# ASL1001.net
KiCad netlist of a schematic drawn in EAGLE
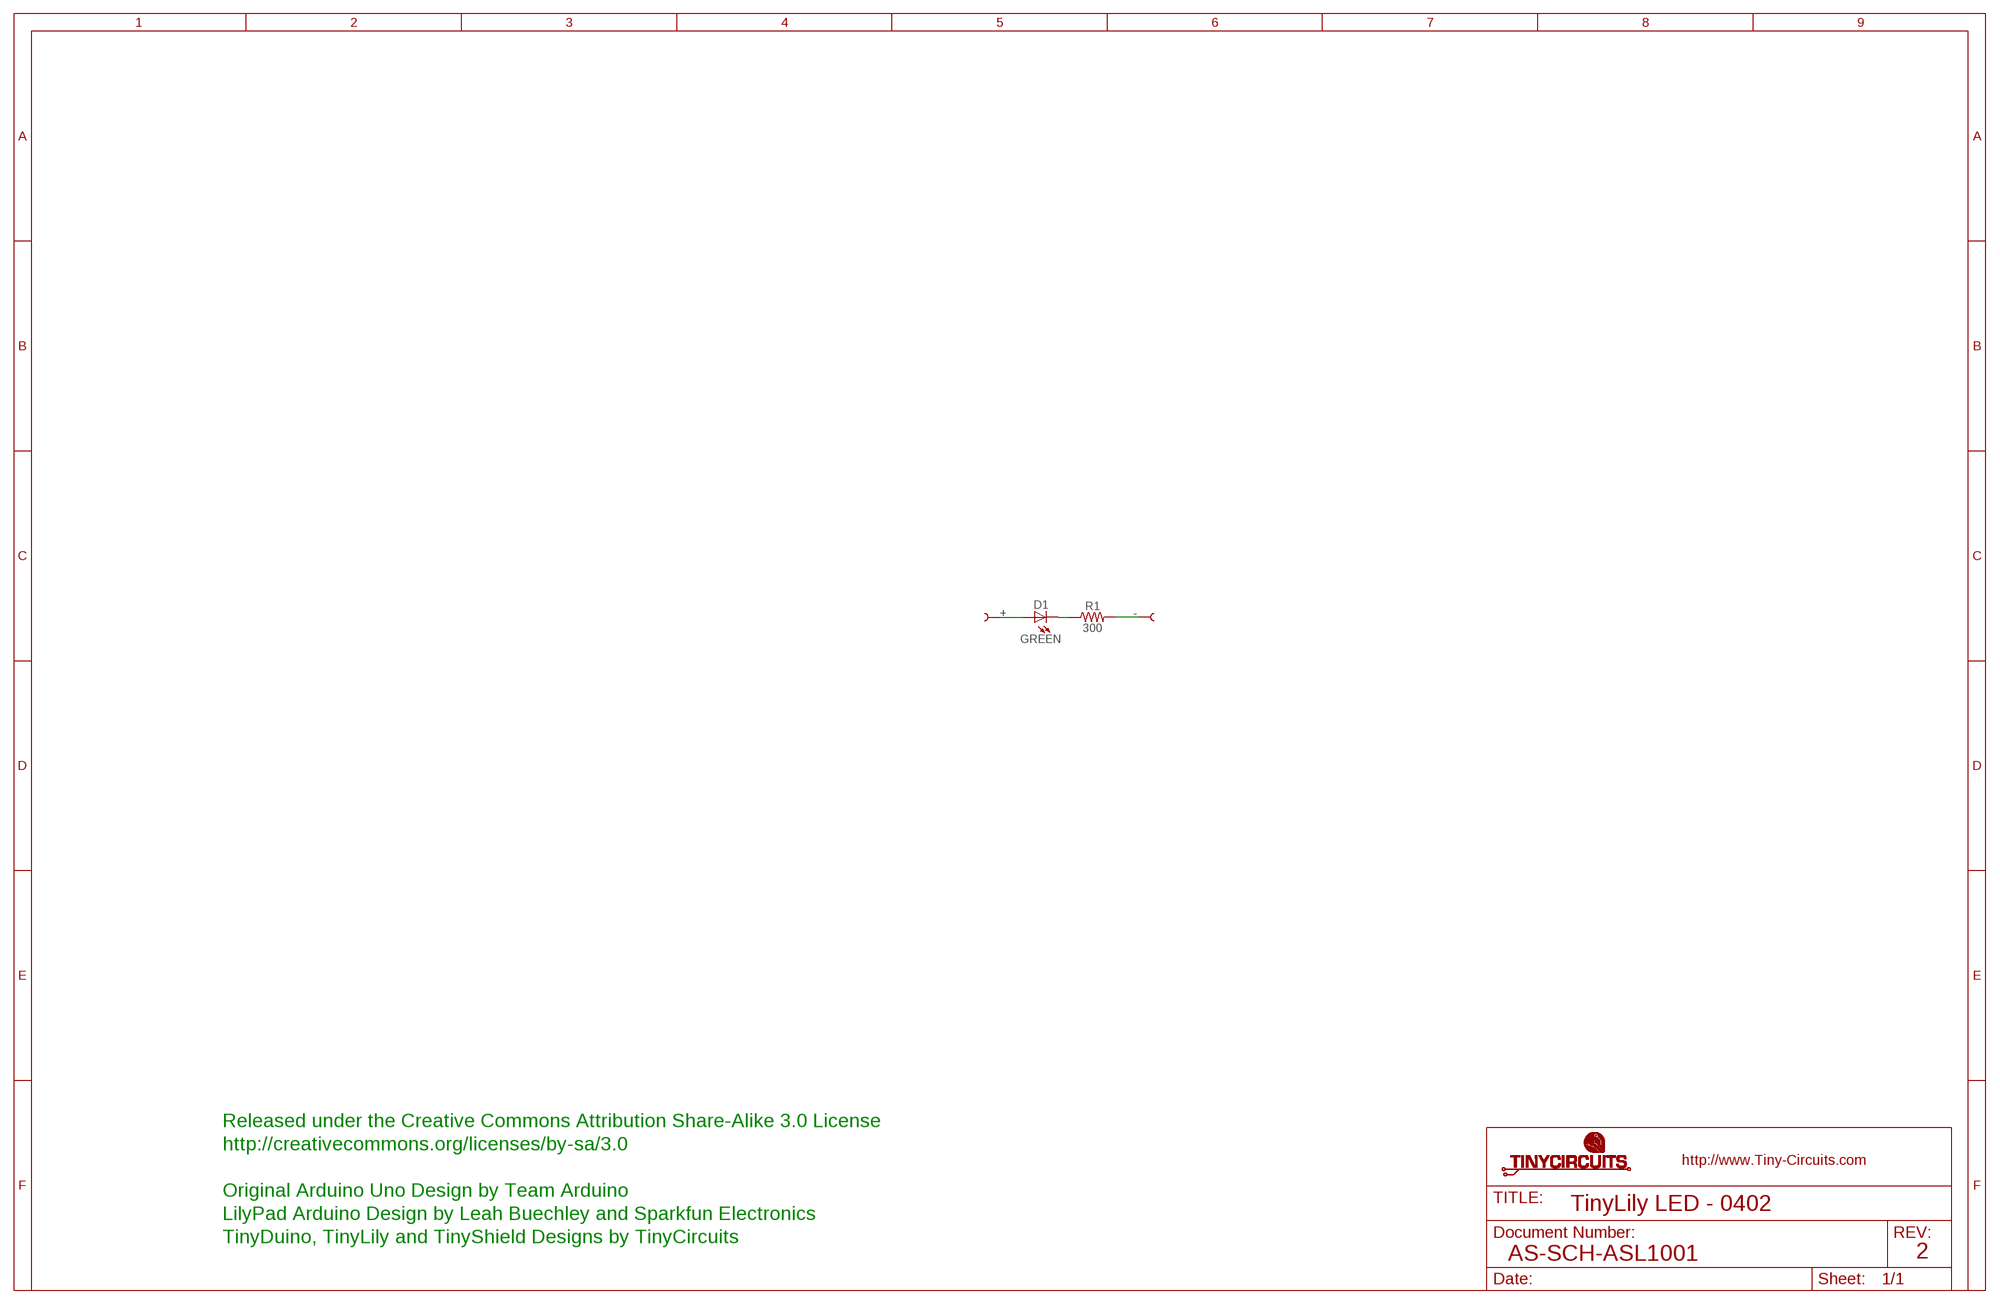
[diagram p0: schematic, sheet 1]

(export (version "E")
  (design (tool "Eeschema 10.0.6"))
  (components
    (comp (ref "D1")
      (value "GREEN")
      (footprint "eagle-import:0402_LED")
      (fields (field (name "PARTNO") "AS-ITM-00038"))
      (libsource (lib "eagle-import") (part "AS-ITM-00038"))
    )
    (comp (ref "R1")
      (value "300")
      (footprint "eagle-import:0402")
      (fields (field (name "PARTNO") "AS-ITM-00016"))
      (libsource (lib "eagle-import") (part "AS-ITM-00016"))
    )
    (comp (ref "U$1")
      (value "SEWTABTH_0402")
      (footprint "eagle-import:SEWTAP_TH_0402")
      (libsource (lib "eagle-import") (part "SEWTABTH_0402"))
    )
    (comp (ref "U$7")
      (value "SEWTABTH_0402")
      (footprint "eagle-import:SEWTAP_TH_0402")
      (libsource (lib "eagle-import") (part "SEWTABTH_0402"))
    )
  )
  (nets
    (net (code "1") (name "/+") (class "Default")
      (node (ref "D1") (pin "1") (pinfunction "A_1") (pintype "passive"))
      (node (ref "U$7") (pin "1") (pinfunction "1_1") (pintype "bidirectional"))
    )
    (net (code "2") (name "/-") (class "Default")
      (node (ref "R1") (pin "2") (pinfunction "2_2") (pintype "passive"))
      (node (ref "U$1") (pin "1") (pinfunction "1_1") (pintype "bidirectional"))
    )
    (net (code "3") (name "Net-(D1-C)") (class "Default")
      (node (ref "D1") (pin "2") (pinfunction "C_2") (pintype "passive"))
      (node (ref "R1") (pin "1") (pinfunction "1_1") (pintype "passive"))
    )
  )
)
